# Expanders.net
KiCad netlist of a schematic drawn in Altium Designer
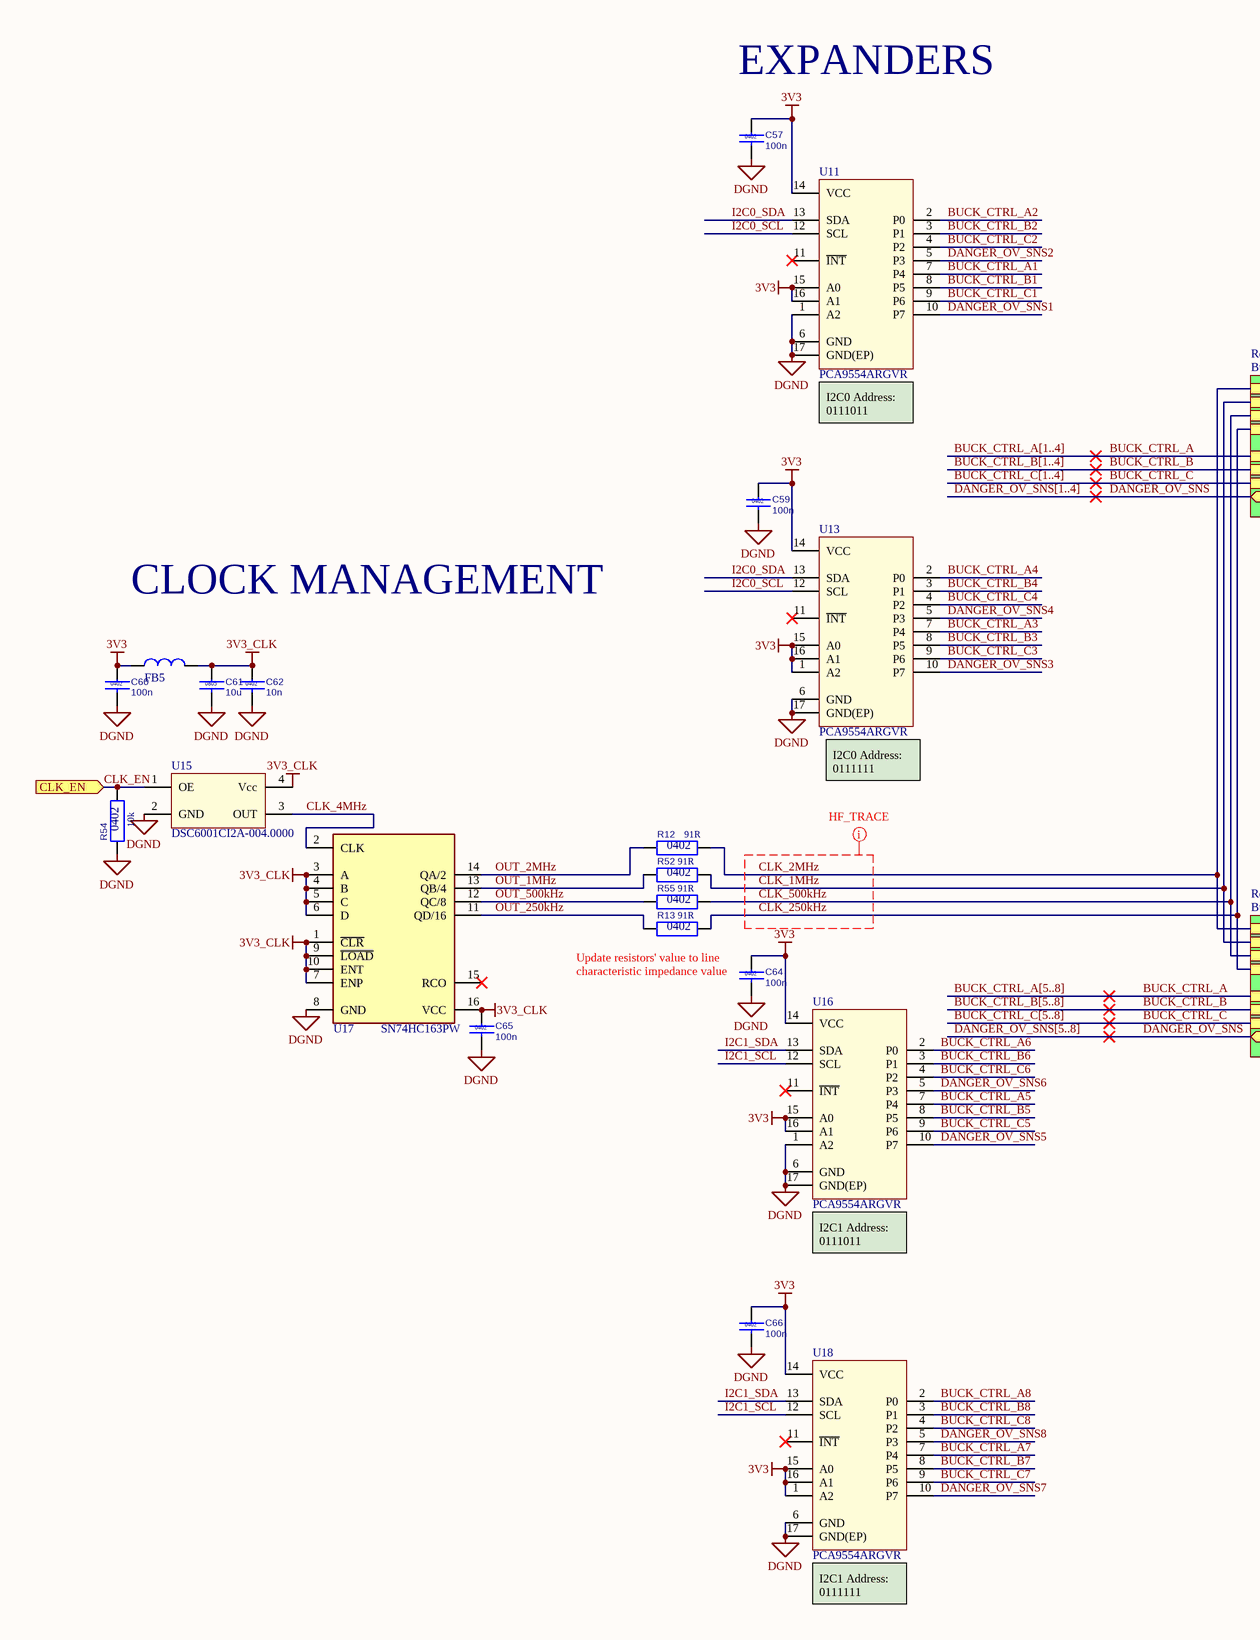
[diagram p0: Expanders.SchDoc, left]
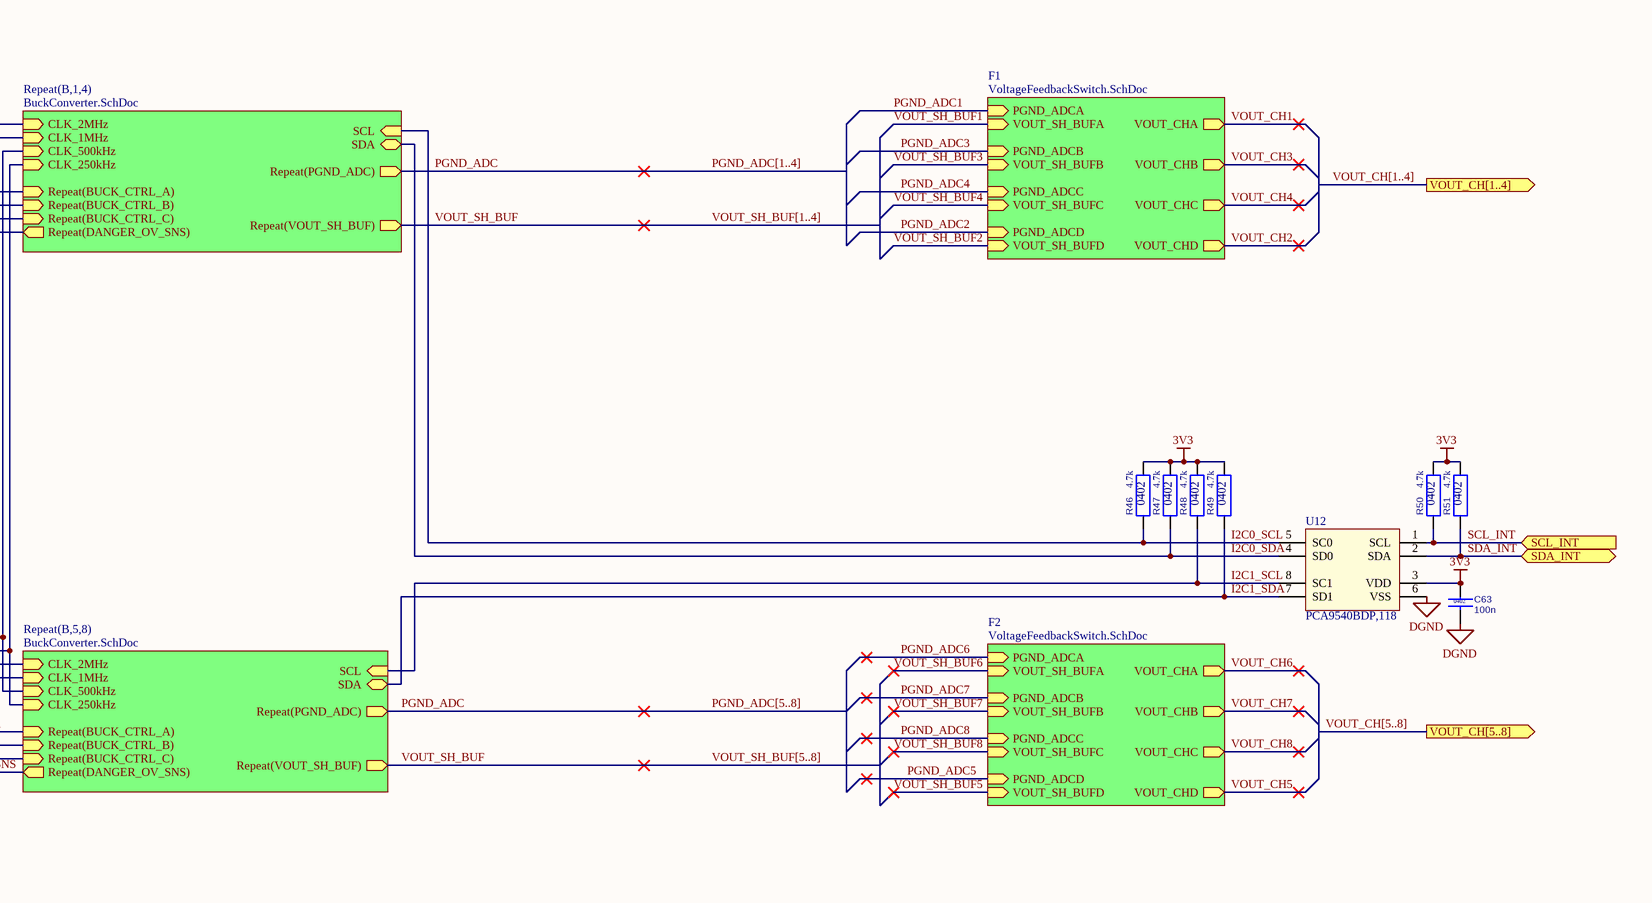
[diagram p1: Expanders.SchDoc, right]

(export (version "E")
  (design (tool "Eeschema 10.0.6"))
  (components
    (comp (ref "C57")
      (value "100n")
      (footprint "CC0402M")
      (description "Chip ceramic capacitor")
      (fields
        (field (name "CASE") "0402")
        (field (name "PARTNUMBER") "CC0402K-X7R-25V-100N-M")
        (field (name "MANUFACTURER") "Murata")
        (field (name "PUBLISHER") "alexey.savchenko")
      )
      (libsource (lib "AltiumLib") (part "Capacitor_nonpolar"))
    )
    (comp (ref "C59")
      (value "100n")
      (footprint "CC0402M")
      (description "Chip ceramic capacitor")
      (fields
        (field (name "CASE") "0402")
        (field (name "PARTNUMBER") "CC0402K-X7R-25V-100N-M")
        (field (name "MANUFACTURER") "Murata")
        (field (name "PUBLISHER") "alexey.savchenko")
      )
      (libsource (lib "AltiumLib") (part "Capacitor_nonpolar"))
    )
    (comp (ref "C60")
      (value "100n")
      (footprint "CC0402M")
      (description "Chip ceramic capacitor")
      (fields
        (field (name "CASE") "0402")
        (field (name "PARTNUMBER") "CC0402K-X7R-25V-100N-M")
        (field (name "MANUFACTURER") "Murata")
        (field (name "PUBLISHER") "alexey.savchenko")
      )
      (libsource (lib "AltiumLib") (part "Capacitor_nonpolar"))
    )
    (comp (ref "C61")
      (value "10u")
      (footprint "CC0805M")
      (description "Chip ceramic capacitor")
      (fields
        (field (name "CASE") "0805")
        (field (name "PARTNUMBER") "CC0805K-X7R-6V3-10U-M")
        (field (name "MANUFACTURER") "Samsung")
        (field (name "PUBLISHER") "alexey.savchenko")
      )
      (libsource (lib "AltiumLib") (part "Capacitor_nonpolar"))
    )
    (comp (ref "C62")
      (value "10n")
      (footprint "CC0402M")
      (description "Chip ceramic capacitor")
      (fields
        (field (name "CASE") "0402")
        (field (name "PARTNUMBER") "CC0402K-X7R-50V-10N-M")
        (field (name "MANUFACTURER") "Yageo")
        (field (name "PUBLISHER") "alexey.savchenko")
      )
      (libsource (lib "AltiumLib") (part "Capacitor_nonpolar"))
    )
    (comp (ref "C63")
      (value "100n")
      (footprint "CC0402M")
      (description "Chip ceramic capacitor")
      (fields
        (field (name "CASE") "0402")
        (field (name "PARTNUMBER") "CC0402K-X7R-25V-100N-M")
        (field (name "MANUFACTURER") "Murata")
        (field (name "PUBLISHER") "alexey.savchenko")
      )
      (libsource (lib "AltiumLib") (part "Capacitor_nonpolar"))
    )
    (comp (ref "C64")
      (value "100n")
      (footprint "CC0402M")
      (description "Chip ceramic capacitor")
      (fields
        (field (name "CASE") "0402")
        (field (name "PARTNUMBER") "CC0402K-X7R-25V-100N-M")
        (field (name "MANUFACTURER") "Murata")
        (field (name "PUBLISHER") "alexey.savchenko")
      )
      (libsource (lib "AltiumLib") (part "Capacitor_nonpolar"))
    )
    (comp (ref "C65")
      (value "100n")
      (footprint "CC0402M")
      (description "Chip ceramic capacitor")
      (fields
        (field (name "CASE") "0402")
        (field (name "PARTNUMBER") "CC0402K-X7R-25V-100N-M")
        (field (name "MANUFACTURER") "Murata")
        (field (name "PUBLISHER") "alexey.savchenko")
      )
      (libsource (lib "AltiumLib") (part "Capacitor_nonpolar"))
    )
    (comp (ref "C66")
      (value "100n")
      (footprint "CC0402M")
      (description "Chip ceramic capacitor")
      (fields
        (field (name "CASE") "0402")
        (field (name "PARTNUMBER") "CC0402K-X7R-25V-100N-M")
        (field (name "MANUFACTURER") "Murata")
        (field (name "PUBLISHER") "alexey.savchenko")
      )
      (libsource (lib "AltiumLib") (part "Capacitor_nonpolar"))
    )
    (comp (ref "FB5")
      (value "BLM18HG102SN1D")
      (footprint "FB0603M")
      (description "FERRITE BEAD 1 KOHM 0603 1LN")
      (fields (field (name "MANUFACTURER") "Murata") (field (name "PUBLISHER") "alexey.savchenko"))
      (libsource (lib "AltiumLib") (part "FerriteBead"))
    )
    (comp (ref "R12")
      (value "91R")
      (footprint "RC0402M")
      (description "Chip resistor")
      (fields
        (field (name "CASE") "0402")
        (field (name "PARTNUMBER") "RC0402F-91R-M")
        (field (name "POWER") "0.063W")
        (field (name "PUBLISHER") "alexey.savchenko")
      )
      (libsource (lib "AltiumLib") (part "Resistor"))
    )
    (comp (ref "R13")
      (value "91R")
      (footprint "RC0402M")
      (description "Chip resistor")
      (fields
        (field (name "CASE") "0402")
        (field (name "PARTNUMBER") "RC0402F-91R-M")
        (field (name "POWER") "0.063W")
        (field (name "PUBLISHER") "alexey.savchenko")
      )
      (libsource (lib "AltiumLib") (part "Resistor"))
    )
    (comp (ref "R46")
      (value "4.7k")
      (footprint "RC0402M")
      (description "Chip resistor")
      (fields
        (field (name "CASE") "0402")
        (field (name "PARTNUMBER") "RC0402F-4K7-M")
        (field (name "POWER") "0.063W")
        (field (name "PUBLISHER") "alexey.savchenko")
      )
      (libsource (lib "AltiumLib") (part "Resistor"))
    )
    (comp (ref "R47")
      (value "4.7k")
      (footprint "RC0402M")
      (description "Chip resistor")
      (fields
        (field (name "CASE") "0402")
        (field (name "PARTNUMBER") "RC0402F-4K7-M")
        (field (name "POWER") "0.063W")
        (field (name "PUBLISHER") "alexey.savchenko")
      )
      (libsource (lib "AltiumLib") (part "Resistor"))
    )
    (comp (ref "R48")
      (value "4.7k")
      (footprint "RC0402M")
      (description "Chip resistor")
      (fields
        (field (name "CASE") "0402")
        (field (name "PARTNUMBER") "RC0402F-4K7-M")
        (field (name "POWER") "0.063W")
        (field (name "PUBLISHER") "alexey.savchenko")
      )
      (libsource (lib "AltiumLib") (part "Resistor"))
    )
    (comp (ref "R49")
      (value "4.7k")
      (footprint "RC0402M")
      (description "Chip resistor")
      (fields
        (field (name "CASE") "0402")
        (field (name "PARTNUMBER") "RC0402F-4K7-M")
        (field (name "POWER") "0.063W")
        (field (name "PUBLISHER") "alexey.savchenko")
      )
      (libsource (lib "AltiumLib") (part "Resistor"))
    )
    (comp (ref "R50")
      (value "4.7k")
      (footprint "RC0402M")
      (description "Chip resistor")
      (fields
        (field (name "CASE") "0402")
        (field (name "PARTNUMBER") "RC0402F-4K7-M")
        (field (name "POWER") "0.063W")
        (field (name "PUBLISHER") "alexey.savchenko")
      )
      (libsource (lib "AltiumLib") (part "Resistor"))
    )
    (comp (ref "R51")
      (value "4.7k")
      (footprint "RC0402M")
      (description "Chip resistor")
      (fields
        (field (name "CASE") "0402")
        (field (name "PARTNUMBER") "RC0402F-4K7-M")
        (field (name "POWER") "0.063W")
        (field (name "PUBLISHER") "alexey.savchenko")
      )
      (libsource (lib "AltiumLib") (part "Resistor"))
    )
    (comp (ref "R52")
      (value "91R")
      (footprint "RC0402M")
      (description "Chip resistor")
      (fields
        (field (name "CASE") "0402")
        (field (name "PARTNUMBER") "RC0402F-91R-M")
        (field (name "POWER") "0.063W")
        (field (name "PUBLISHER") "alexey.savchenko")
      )
      (libsource (lib "AltiumLib") (part "Resistor"))
    )
    (comp (ref "R54")
      (value "10k")
      (footprint "RC0402M")
      (description "Chip resistor")
      (fields
        (field (name "CASE") "0402")
        (field (name "PARTNUMBER") "RC0402F-10K-M")
        (field (name "MANUFACTURER") "Yageo")
        (field (name "PUBLISHER") "alexey.savchenko")
      )
      (libsource (lib "AltiumLib") (part "Resistor"))
    )
    (comp (ref "R55")
      (value "91R")
      (footprint "RC0402M")
      (description "Chip resistor")
      (fields
        (field (name "CASE") "0402")
        (field (name "PARTNUMBER") "RC0402F-91R-M")
        (field (name "POWER") "0.063W")
        (field (name "PUBLISHER") "alexey.savchenko")
      )
      (libsource (lib "AltiumLib") (part "Resistor"))
    )
    (comp (ref "U11")
      (value "PCA9554ARGVR")
      (footprint "VQFN-16(RGV)")
      (description "I/O Expander 8 I²C, SMBus 400kHz 16-VQFN (4x4)")
      (fields (field (name "MANUFACTURER") "TI") (field (name "PUBLISHER") "alexey.savchenko"))
      (libsource (lib "AltiumLib") (part "PCA9554ARGVR"))
    )
    (comp (ref "U12")
      (value "PCA9540BDP,118")
      (footprint "TSSOP-8")
      (description "IC INTERFACE SPECIALIZED 8TSSOP")
      (fields (field (name "MANUFACTURER") "NXP") (field (name "PUBLISHER") "alexey.savchenko"))
      (libsource (lib "AltiumLib") (part "PCA9540B"))
    )
    (comp (ref "U13")
      (value "PCA9554ARGVR")
      (footprint "VQFN-16(RGV)")
      (description "I/O Expander 8 I²C, SMBus 400kHz 16-VQFN (4x4)")
      (fields (field (name "MANUFACTURER") "TI") (field (name "PUBLISHER") "alexey.savchenko"))
      (libsource (lib "AltiumLib") (part "PCA9554ARGVR"))
    )
    (comp (ref "U15")
      (value "DSC6001CI2A-004.0000")
      (footprint "CDFN3225-4LD")
      (description "4MHz XO (Standard) CMOS Oscillator 1.8V ~ 3.3V Enable/Disable 4-SMD, No Lead")
      (fields (field (name "MANUFACTURER") "Microchip") (field (name "PUBLISHER") "alexey.savchenko"))
      (libsource (lib "AltiumLib") (part "DSC6001"))
    )
    (comp (ref "U16")
      (value "PCA9554ARGVR")
      (footprint "VQFN-16(RGV)")
      (description "I/O Expander 8 I²C, SMBus 400kHz 16-VQFN (4x4)")
      (fields (field (name "MANUFACTURER") "TI") (field (name "PUBLISHER") "alexey.savchenko"))
      (libsource (lib "AltiumLib") (part "PCA9554ARGVR"))
    )
    (comp (ref "U17")
      (value "SN74HC163PW")
      (footprint "TSSOP-16")
      (description "Counter IC Binary Counter 1 Element 4 Bit Positive Edge 16-TSSOP")
      (fields (field (name "MANUFACTURER") "TI") (field (name "PUBLISHER") "alexey.savchenko"))
      (libsource (lib "AltiumLib") (part "74HC163PW"))
    )
    (comp (ref "U18")
      (value "PCA9554ARGVR")
      (footprint "VQFN-16(RGV)")
      (description "I/O Expander 8 I²C, SMBus 400kHz 16-VQFN (4x4)")
      (fields (field (name "MANUFACTURER") "TI") (field (name "PUBLISHER") "alexey.savchenko"))
      (libsource (lib "AltiumLib") (part "PCA9554ARGVR"))
    )
  )
  (nets
    (net (code "2") (name "/BUCK_CTRL_A1") (class "Default")
      (node (ref "U11") (pin "7") (pinfunction "P4_7") (pintype "passive"))
    )
    (net (code "3") (name "/BUCK_CTRL_A2") (class "Default")
      (node (ref "U11") (pin "2") (pinfunction "P0_2") (pintype "passive"))
    )
    (net (code "4") (name "/BUCK_CTRL_A3") (class "Default")
      (node (ref "U13") (pin "7") (pinfunction "P4_7") (pintype "passive"))
    )
    (net (code "5") (name "/BUCK_CTRL_A4") (class "Default")
      (node (ref "U13") (pin "2") (pinfunction "P0_2") (pintype "passive"))
    )
    (net (code "6") (name "/BUCK_CTRL_A5") (class "Default")
      (node (ref "U16") (pin "7") (pinfunction "P4_7") (pintype "passive"))
    )
    (net (code "7") (name "/BUCK_CTRL_A6") (class "Default")
      (node (ref "U16") (pin "2") (pinfunction "P0_2") (pintype "passive"))
    )
    (net (code "8") (name "/BUCK_CTRL_A7") (class "Default")
      (node (ref "U18") (pin "7") (pinfunction "P4_7") (pintype "passive"))
    )
    (net (code "9") (name "/BUCK_CTRL_A8") (class "Default")
      (node (ref "U18") (pin "2") (pinfunction "P0_2") (pintype "passive"))
    )
    (net (code "13") (name "/BUCK_CTRL_B1") (class "Default")
      (node (ref "U11") (pin "8") (pinfunction "P5_8") (pintype "passive"))
    )
    (net (code "14") (name "/BUCK_CTRL_B2") (class "Default")
      (node (ref "U11") (pin "3") (pinfunction "P1_3") (pintype "passive"))
    )
    (net (code "15") (name "/BUCK_CTRL_B3") (class "Default")
      (node (ref "U13") (pin "8") (pinfunction "P5_8") (pintype "passive"))
    )
    (net (code "16") (name "/BUCK_CTRL_B4") (class "Default")
      (node (ref "U13") (pin "3") (pinfunction "P1_3") (pintype "passive"))
    )
    (net (code "17") (name "/BUCK_CTRL_B5") (class "Default")
      (node (ref "U16") (pin "8") (pinfunction "P5_8") (pintype "passive"))
    )
    (net (code "18") (name "/BUCK_CTRL_B6") (class "Default")
      (node (ref "U16") (pin "3") (pinfunction "P1_3") (pintype "passive"))
    )
    (net (code "19") (name "/BUCK_CTRL_B7") (class "Default")
      (node (ref "U18") (pin "8") (pinfunction "P5_8") (pintype "passive"))
    )
    (net (code "20") (name "/BUCK_CTRL_B8") (class "Default")
      (node (ref "U18") (pin "3") (pinfunction "P1_3") (pintype "passive"))
    )
    (net (code "24") (name "/BUCK_CTRL_C1") (class "Default")
      (node (ref "U11") (pin "9") (pinfunction "P6_9") (pintype "passive"))
    )
    (net (code "25") (name "/BUCK_CTRL_C2") (class "Default")
      (node (ref "U11") (pin "4") (pinfunction "P2_4") (pintype "passive"))
    )
    (net (code "26") (name "/BUCK_CTRL_C3") (class "Default")
      (node (ref "U13") (pin "9") (pinfunction "P6_9") (pintype "passive"))
    )
    (net (code "27") (name "/BUCK_CTRL_C4") (class "Default")
      (node (ref "U13") (pin "4") (pinfunction "P2_4") (pintype "passive"))
    )
    (net (code "28") (name "/BUCK_CTRL_C5") (class "Default")
      (node (ref "U16") (pin "9") (pinfunction "P6_9") (pintype "passive"))
    )
    (net (code "29") (name "/BUCK_CTRL_C6") (class "Default")
      (node (ref "U16") (pin "4") (pinfunction "P2_4") (pintype "passive"))
    )
    (net (code "30") (name "/BUCK_CTRL_C7") (class "Default")
      (node (ref "U18") (pin "9") (pinfunction "P6_9") (pintype "passive"))
    )
    (net (code "31") (name "/BUCK_CTRL_C8") (class "Default")
      (node (ref "U18") (pin "4") (pinfunction "P2_4") (pintype "passive"))
    )
    (net (code "34") (name "/CLK_1MHz") (class "Default")
      (node (ref "R52") (pin "2") (pinfunction "2_2") (pintype "passive"))
    )
    (net (code "35") (name "/CLK_2MHz") (class "Default")
      (node (ref "R12") (pin "2") (pinfunction "2_2") (pintype "passive"))
    )
    (net (code "36") (name "/CLK_4MHz") (class "Default")
      (node (ref "U15") (pin "3") (pinfunction "OUT_3") (pintype "passive"))
      (node (ref "U17") (pin "2") (pinfunction "CLK_2") (pintype "passive"))
    )
    (net (code "37") (name "/CLK_250kHz") (class "Default")
      (node (ref "R13") (pin "2") (pinfunction "2_2") (pintype "passive"))
    )
    (net (code "38") (name "/CLK_500kHz") (class "Default")
      (node (ref "R55") (pin "2") (pinfunction "2_2") (pintype "passive"))
    )
    (net (code "39") (name "/CLK_EN") (class "Default")
      (node (ref "R54") (pin "2") (pinfunction "2_2") (pintype "passive"))
      (node (ref "U15") (pin "1") (pinfunction "OE_1") (pintype "passive"))
    )
    (net (code "41") (name "/DANGER_OV_SNS1") (class "Default")
      (node (ref "U11") (pin "10") (pinfunction "P7_10") (pintype "passive"))
    )
    (net (code "42") (name "/DANGER_OV_SNS2") (class "Default")
      (node (ref "U11") (pin "5") (pinfunction "P3_5") (pintype "passive"))
    )
    (net (code "43") (name "/DANGER_OV_SNS3") (class "Default")
      (node (ref "U13") (pin "10") (pinfunction "P7_10") (pintype "passive"))
    )
    (net (code "44") (name "/DANGER_OV_SNS4") (class "Default")
      (node (ref "U13") (pin "5") (pinfunction "P3_5") (pintype "passive"))
    )
    (net (code "45") (name "/DANGER_OV_SNS5") (class "Default")
      (node (ref "U16") (pin "10") (pinfunction "P7_10") (pintype "passive"))
    )
    (net (code "46") (name "/DANGER_OV_SNS6") (class "Default")
      (node (ref "U16") (pin "5") (pinfunction "P3_5") (pintype "passive"))
    )
    (net (code "47") (name "/DANGER_OV_SNS7") (class "Default")
      (node (ref "U18") (pin "10") (pinfunction "P7_10") (pintype "passive"))
    )
    (net (code "48") (name "/DANGER_OV_SNS8") (class "Default")
      (node (ref "U18") (pin "5") (pinfunction "P3_5") (pintype "passive"))
    )
    (net (code "51") (name "/I2C0_SCL") (class "Default")
      (node (ref "R46") (pin "1") (pinfunction "1_1") (pintype "passive"))
      (node (ref "U11") (pin "12") (pinfunction "SCL_12") (pintype "passive"))
      (node (ref "U12") (pin "5") (pinfunction "SC0_5") (pintype "passive"))
      (node (ref "U13") (pin "12") (pinfunction "SCL_12") (pintype "passive"))
    )
    (net (code "52") (name "/I2C0_SDA") (class "Default")
      (node (ref "R47") (pin "1") (pinfunction "1_1") (pintype "passive"))
      (node (ref "U11") (pin "13") (pinfunction "SDA_13") (pintype "passive"))
      (node (ref "U12") (pin "4") (pinfunction "SD0_4") (pintype "passive"))
      (node (ref "U13") (pin "13") (pinfunction "SDA_13") (pintype "passive"))
    )
    (net (code "53") (name "/I2C1_SCL") (class "Default")
      (node (ref "R48") (pin "1") (pinfunction "1_1") (pintype "passive"))
      (node (ref "U12") (pin "8") (pinfunction "SC1_8") (pintype "passive"))
      (node (ref "U16") (pin "12") (pinfunction "SCL_12") (pintype "passive"))
      (node (ref "U18") (pin "12") (pinfunction "SCL_12") (pintype "passive"))
    )
    (net (code "54") (name "/I2C1_SDA") (class "Default")
      (node (ref "R49") (pin "1") (pinfunction "1_1") (pintype "passive"))
      (node (ref "U12") (pin "7") (pinfunction "SD1_7") (pintype "passive"))
      (node (ref "U16") (pin "13") (pinfunction "SDA_13") (pintype "passive"))
      (node (ref "U18") (pin "13") (pinfunction "SDA_13") (pintype "passive"))
    )
    (net (code "55") (name "/OUT_1MHz") (class "Default")
      (node (ref "R52") (pin "1") (pinfunction "1_1") (pintype "passive"))
      (node (ref "U17") (pin "13") (pinfunction "QB/4_13") (pintype "passive"))
    )
    (net (code "56") (name "/OUT_2MHz") (class "Default")
      (node (ref "R12") (pin "1") (pinfunction "1_1") (pintype "passive"))
      (node (ref "U17") (pin "14") (pinfunction "QA/2_14") (pintype "passive"))
    )
    (net (code "57") (name "/OUT_250kHz") (class "Default")
      (node (ref "R13") (pin "1") (pinfunction "1_1") (pintype "passive"))
      (node (ref "U17") (pin "11") (pinfunction "QD/16_11") (pintype "passive"))
    )
    (net (code "58") (name "/OUT_500kHz") (class "Default")
      (node (ref "R55") (pin "1") (pinfunction "1_1") (pintype "passive"))
      (node (ref "U17") (pin "12") (pinfunction "QC/8_12") (pintype "passive"))
    )
    (net (code "70") (name "/SCL_INT") (class "Default")
      (node (ref "R50") (pin "1") (pinfunction "1_1") (pintype "passive"))
      (node (ref "U12") (pin "1") (pinfunction "SCL_1") (pintype "passive"))
    )
    (net (code "71") (name "/SDA_INT") (class "Default")
      (node (ref "R51") (pin "1") (pinfunction "1_1") (pintype "passive"))
      (node (ref "U12") (pin "2") (pinfunction "SDA_2") (pintype "passive"))
    )
    (net (code "93") (name "3V3") (class "Default")
      (node (ref "C57") (pin "1") (pinfunction "1_1") (pintype "passive"))
      (node (ref "C59") (pin "1") (pinfunction "1_1") (pintype "passive"))
      (node (ref "C60") (pin "1") (pinfunction "1_1") (pintype "passive"))
      (node (ref "C63") (pin "1") (pinfunction "1_1") (pintype "passive"))
      (node (ref "C64") (pin "1") (pinfunction "1_1") (pintype "passive"))
      (node (ref "C66") (pin "1") (pinfunction "1_1") (pintype "passive"))
      (node (ref "FB5") (pin "1") (pinfunction "1_1") (pintype "passive"))
      (node (ref "R46") (pin "2") (pinfunction "2_2") (pintype "passive"))
      (node (ref "R47") (pin "2") (pinfunction "2_2") (pintype "passive"))
      (node (ref "R48") (pin "2") (pinfunction "2_2") (pintype "passive"))
      (node (ref "R49") (pin "2") (pinfunction "2_2") (pintype "passive"))
      (node (ref "R50") (pin "2") (pinfunction "2_2") (pintype "passive"))
      (node (ref "R51") (pin "2") (pinfunction "2_2") (pintype "passive"))
      (node (ref "U11") (pin "14") (pinfunction "VCC_14") (pintype "passive"))
      (node (ref "U11") (pin "15") (pinfunction "A0_15") (pintype "passive"))
      (node (ref "U11") (pin "16") (pinfunction "A1_16") (pintype "passive"))
      (node (ref "U12") (pin "3") (pinfunction "VDD_3") (pintype "passive"))
      (node (ref "U13") (pin "1") (pinfunction "A2_1") (pintype "passive"))
      (node (ref "U13") (pin "14") (pinfunction "VCC_14") (pintype "passive"))
      (node (ref "U13") (pin "15") (pinfunction "A0_15") (pintype "passive"))
      (node (ref "U13") (pin "16") (pinfunction "A1_16") (pintype "passive"))
      (node (ref "U16") (pin "14") (pinfunction "VCC_14") (pintype "passive"))
      (node (ref "U16") (pin "15") (pinfunction "A0_15") (pintype "passive"))
      (node (ref "U16") (pin "16") (pinfunction "A1_16") (pintype "passive"))
      (node (ref "U18") (pin "1") (pinfunction "A2_1") (pintype "passive"))
      (node (ref "U18") (pin "14") (pinfunction "VCC_14") (pintype "passive"))
      (node (ref "U18") (pin "15") (pinfunction "A0_15") (pintype "passive"))
      (node (ref "U18") (pin "16") (pinfunction "A1_16") (pintype "passive"))
    )
    (net (code "94") (name "3V3_CLK") (class "Default")
      (node (ref "C61") (pin "1") (pinfunction "1_1") (pintype "passive"))
      (node (ref "C62") (pin "1") (pinfunction "1_1") (pintype "passive"))
      (node (ref "C65") (pin "1") (pinfunction "1_1") (pintype "passive"))
      (node (ref "FB5") (pin "2") (pinfunction "2_2") (pintype "passive"))
      (node (ref "U15") (pin "4") (pinfunction "Vcc_4") (pintype "passive"))
      (node (ref "U17") (pin "1") (pinfunction "~{CLR}_1") (pintype "passive"))
      (node (ref "U17") (pin "10") (pinfunction "ENT_10") (pintype "passive"))
      (node (ref "U17") (pin "16") (pinfunction "VCC_16") (pintype "passive"))
      (node (ref "U17") (pin "3") (pinfunction "A_3") (pintype "passive"))
      (node (ref "U17") (pin "4") (pinfunction "B_4") (pintype "passive"))
      (node (ref "U17") (pin "5") (pinfunction "C_5") (pintype "passive"))
      (node (ref "U17") (pin "6") (pinfunction "D_6") (pintype "passive"))
      (node (ref "U17") (pin "7") (pinfunction "ENP_7") (pintype "passive"))
      (node (ref "U17") (pin "9") (pinfunction "~{LOAD}_9") (pintype "passive"))
    )
    (net (code "95") (name "DGND") (class "Default")
      (node (ref "C57") (pin "2") (pinfunction "2_2") (pintype "passive"))
      (node (ref "C59") (pin "2") (pinfunction "2_2") (pintype "passive"))
      (node (ref "C60") (pin "2") (pinfunction "2_2") (pintype "passive"))
      (node (ref "C61") (pin "2") (pinfunction "2_2") (pintype "passive"))
      (node (ref "C62") (pin "2") (pinfunction "2_2") (pintype "passive"))
      (node (ref "C63") (pin "2") (pinfunction "2_2") (pintype "passive"))
      (node (ref "C64") (pin "2") (pinfunction "2_2") (pintype "passive"))
      (node (ref "C65") (pin "2") (pinfunction "2_2") (pintype "passive"))
      (node (ref "C66") (pin "2") (pinfunction "2_2") (pintype "passive"))
      (node (ref "R54") (pin "1") (pinfunction "1_1") (pintype "passive"))
      (node (ref "U11") (pin "1") (pinfunction "A2_1") (pintype "passive"))
      (node (ref "U11") (pin "17") (pinfunction "GND(EP)_17") (pintype "passive"))
      (node (ref "U11") (pin "6") (pinfunction "GND_6") (pintype "passive"))
      (node (ref "U12") (pin "6") (pinfunction "VSS_6") (pintype "passive"))
      (node (ref "U13") (pin "17") (pinfunction "GND(EP)_17") (pintype "passive"))
      (node (ref "U13") (pin "6") (pinfunction "GND_6") (pintype "passive"))
      (node (ref "U15") (pin "2") (pinfunction "GND_2") (pintype "passive"))
      (node (ref "U16") (pin "1") (pinfunction "A2_1") (pintype "passive"))
      (node (ref "U16") (pin "17") (pinfunction "GND(EP)_17") (pintype "passive"))
      (node (ref "U16") (pin "6") (pinfunction "GND_6") (pintype "passive"))
      (node (ref "U17") (pin "8") (pinfunction "GND_8") (pintype "passive"))
      (node (ref "U18") (pin "17") (pinfunction "GND(EP)_17") (pintype "passive"))
      (node (ref "U18") (pin "6") (pinfunction "GND_6") (pintype "passive"))
    )
    (net (code "96") (name "unconnected-(U11-~{INT}-Pad11)") (class "Default")
      (node (ref "U11") (pin "11") (pinfunction "~{INT}_11") (pintype "passive+no_connect"))
    )
    (net (code "97") (name "unconnected-(U13-~{INT}-Pad11)") (class "Default")
      (node (ref "U13") (pin "11") (pinfunction "~{INT}_11") (pintype "passive+no_connect"))
    )
    (net (code "98") (name "unconnected-(U16-~{INT}-Pad11)") (class "Default")
      (node (ref "U16") (pin "11") (pinfunction "~{INT}_11") (pintype "passive+no_connect"))
    )
    (net (code "99") (name "unconnected-(U17-RCO-Pad15)") (class "Default")
      (node (ref "U17") (pin "15") (pinfunction "RCO_15") (pintype "passive+no_connect"))
    )
    (net (code "100") (name "unconnected-(U18-~{INT}-Pad11)") (class "Default")
      (node (ref "U18") (pin "11") (pinfunction "~{INT}_11") (pintype "passive+no_connect"))
    )
  )
)
